# stepper_cape.net
KiCad netlist of a schematic drawn in EAGLE
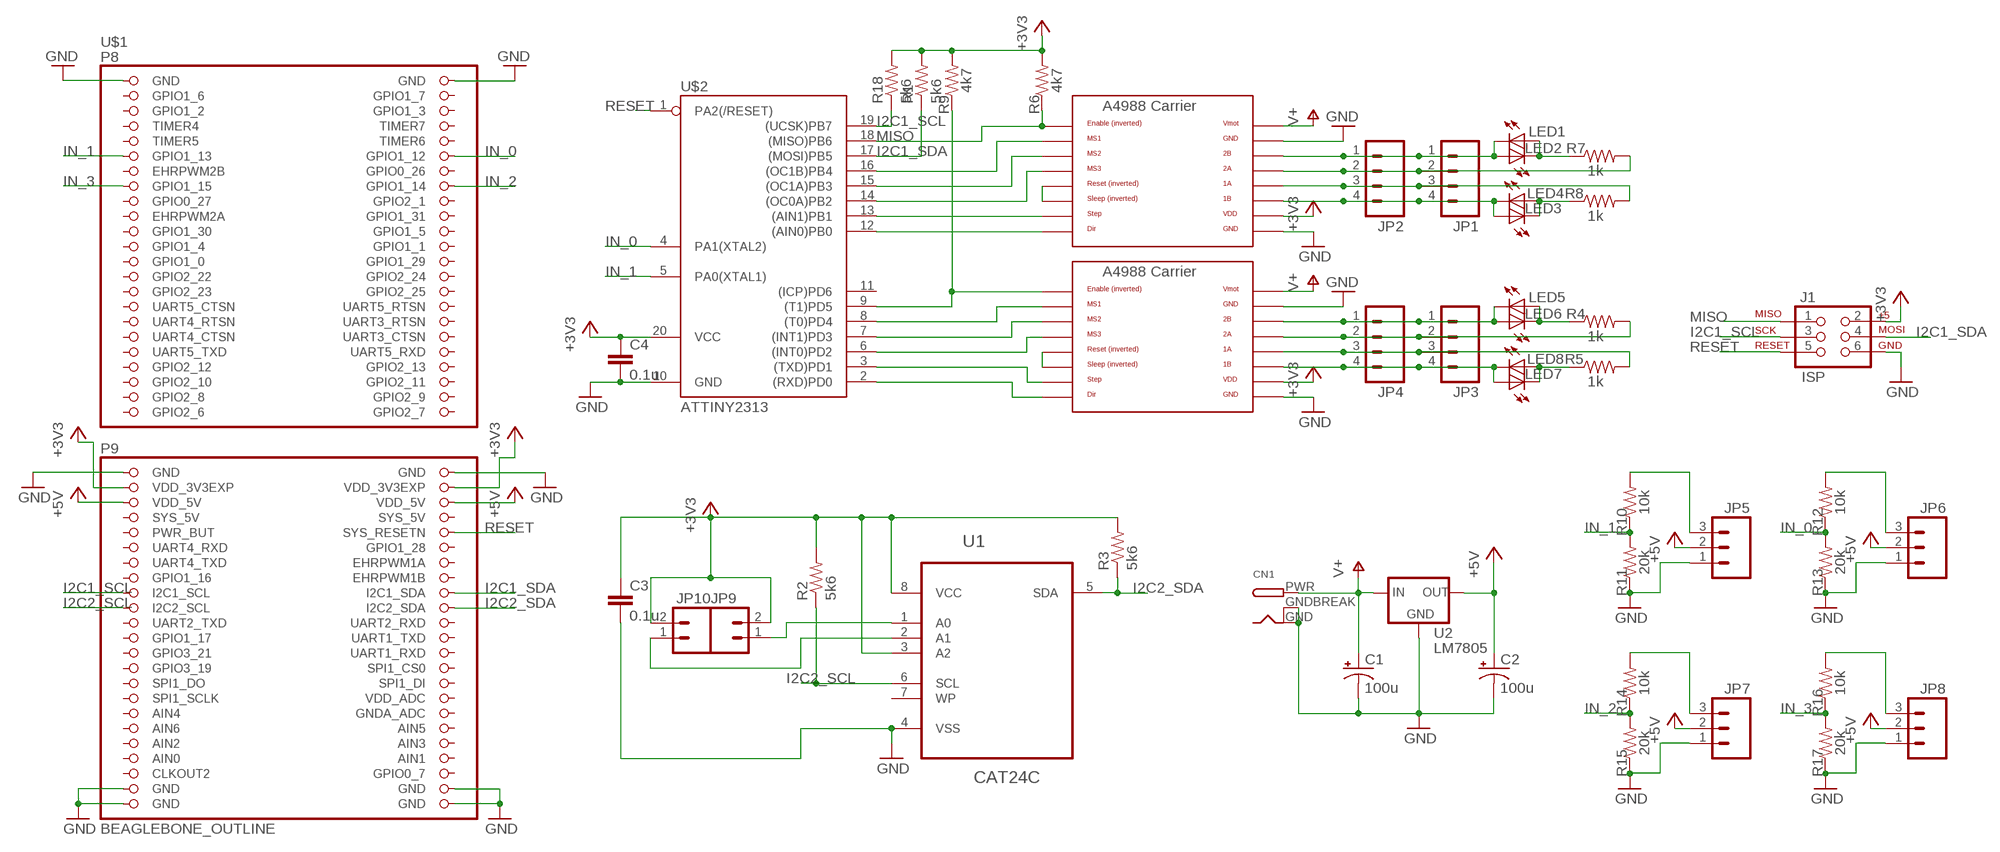
[diagram p0: schematic, sheet 1]

(export (version "E")
  (design (tool "Eeschema 10.0.6"))
  (components
    (comp (ref "C1")
      (value "100u")
      (footprint "eagle-import:E2,5-6")
      (libsource (lib "eagle-import") (part "CPOL-USE2.5-6"))
    )
    (comp (ref "C2")
      (value "100u")
      (footprint "eagle-import:E2,5-6")
      (libsource (lib "eagle-import") (part "CPOL-USE2.5-6"))
    )
    (comp (ref "C3")
      (value "0.1u")
      (footprint "eagle-import:0805")
      (libsource (lib "eagle-import") (part "CAP0805"))
    )
    (comp (ref "C4")
      (value "0.1u")
      (footprint "eagle-import:0805")
      (libsource (lib "eagle-import") (part "CAP0805"))
    )
    (comp (ref "CN1")
      (value "DCBARRELPTH")
      (footprint "eagle-import:DCJACK_2MM_PTH")
      (libsource (lib "eagle-import") (part "DCBARRELPTH"))
    )
    (comp (ref "J1")
      (value "ISP")
      (footprint "eagle-import:2X3")
      (libsource (lib "eagle-import") (part "AVR_SPI_PRG_6PTH"))
    )
    (comp (ref "JP1")
      (value "M04SCREW")
      (footprint "eagle-import:SCREWTERMINAL-3.5MM-4")
      (libsource (lib "eagle-import") (part "M04SCREW"))
    )
    (comp (ref "JP2")
      (value "M04PTH")
      (footprint "eagle-import:1X04")
      (libsource (lib "eagle-import") (part "M04PTH"))
    )
    (comp (ref "JP3")
      (value "M04SCREW")
      (footprint "eagle-import:SCREWTERMINAL-3.5MM-4")
      (libsource (lib "eagle-import") (part "M04SCREW"))
    )
    (comp (ref "JP4")
      (value "M04PTH")
      (footprint "eagle-import:1X04")
      (libsource (lib "eagle-import") (part "M04PTH"))
    )
    (comp (ref "JP5")
      (value "M03PTH")
      (footprint "eagle-import:1X03")
      (libsource (lib "eagle-import") (part "M03PTH"))
    )
    (comp (ref "JP6")
      (value "M03PTH")
      (footprint "eagle-import:1X03")
      (libsource (lib "eagle-import") (part "M03PTH"))
    )
    (comp (ref "JP7")
      (value "M03PTH")
      (footprint "eagle-import:1X03")
      (libsource (lib "eagle-import") (part "M03PTH"))
    )
    (comp (ref "JP8")
      (value "M03PTH")
      (footprint "eagle-import:1X03")
      (libsource (lib "eagle-import") (part "M03PTH"))
    )
    (comp (ref "JP9")
      (value "M02PTH")
      (footprint "eagle-import:1X02")
      (libsource (lib "eagle-import") (part "M02PTH"))
    )
    (comp (ref "JP10")
      (value "M02PTH")
      (footprint "eagle-import:1X02")
      (libsource (lib "eagle-import") (part "M02PTH"))
    )
    (comp (ref "LED1")
      (value "LEDCHIPLED_1206")
      (footprint "eagle-import:CHIPLED_1206")
      (libsource (lib "eagle-import") (part "LEDCHIPLED_1206"))
    )
    (comp (ref "LED2")
      (value "LEDCHIPLED_1206")
      (footprint "eagle-import:CHIPLED_1206")
      (libsource (lib "eagle-import") (part "LEDCHIPLED_1206"))
    )
    (comp (ref "LED3")
      (value "LEDCHIPLED_1206")
      (footprint "eagle-import:CHIPLED_1206")
      (libsource (lib "eagle-import") (part "LEDCHIPLED_1206"))
    )
    (comp (ref "LED4")
      (value "LEDCHIPLED_1206")
      (footprint "eagle-import:CHIPLED_1206")
      (libsource (lib "eagle-import") (part "LEDCHIPLED_1206"))
    )
    (comp (ref "LED5")
      (value "LEDCHIPLED_1206")
      (footprint "eagle-import:CHIPLED_1206")
      (libsource (lib "eagle-import") (part "LEDCHIPLED_1206"))
    )
    (comp (ref "LED6")
      (value "LEDCHIPLED_1206")
      (footprint "eagle-import:CHIPLED_1206")
      (libsource (lib "eagle-import") (part "LEDCHIPLED_1206"))
    )
    (comp (ref "LED7")
      (value "LEDCHIPLED_1206")
      (footprint "eagle-import:CHIPLED_1206")
      (libsource (lib "eagle-import") (part "LEDCHIPLED_1206"))
    )
    (comp (ref "LED8")
      (value "LEDCHIPLED_1206")
      (footprint "eagle-import:CHIPLED_1206")
      (libsource (lib "eagle-import") (part "LEDCHIPLED_1206"))
    )
    (comp (ref "R1")
      (value "5k6")
      (footprint "eagle-import:R0805")
      (libsource (lib "eagle-import") (part "R-US_R0805"))
    )
    (comp (ref "R2")
      (value "5k6")
      (footprint "eagle-import:R0805")
      (libsource (lib "eagle-import") (part "R-US_R0805"))
    )
    (comp (ref "R3")
      (value "5k6")
      (footprint "eagle-import:R0805")
      (libsource (lib "eagle-import") (part "R-US_R0805"))
    )
    (comp (ref "R4")
      (value "1k")
      (footprint "eagle-import:R0805")
      (libsource (lib "eagle-import") (part "R-US_R0805"))
    )
    (comp (ref "R5")
      (value "1k")
      (footprint "eagle-import:R0805")
      (libsource (lib "eagle-import") (part "R-US_R0805"))
    )
    (comp (ref "R6")
      (value "4k7")
      (footprint "eagle-import:R0805")
      (libsource (lib "eagle-import") (part "R-US_R0805"))
    )
    (comp (ref "R7")
      (value "1k")
      (footprint "eagle-import:R0805")
      (libsource (lib "eagle-import") (part "R-US_R0805"))
    )
    (comp (ref "R8")
      (value "1k")
      (footprint "eagle-import:R0805")
      (libsource (lib "eagle-import") (part "R-US_R0805"))
    )
    (comp (ref "R9")
      (value "4k7")
      (footprint "eagle-import:R0805")
      (libsource (lib "eagle-import") (part "R-US_R0805"))
    )
    (comp (ref "R10")
      (value "10k")
      (footprint "eagle-import:R0805")
      (libsource (lib "eagle-import") (part "R-US_R0805"))
    )
    (comp (ref "R11")
      (value "20k")
      (footprint "eagle-import:R0805")
      (libsource (lib "eagle-import") (part "R-US_R0805"))
    )
    (comp (ref "R12")
      (value "10k")
      (footprint "eagle-import:R0805")
      (libsource (lib "eagle-import") (part "R-US_R0805"))
    )
    (comp (ref "R13")
      (value "20k")
      (footprint "eagle-import:R0805")
      (libsource (lib "eagle-import") (part "R-US_R0805"))
    )
    (comp (ref "R14")
      (value "10k")
      (footprint "eagle-import:R0805")
      (libsource (lib "eagle-import") (part "R-US_R0805"))
    )
    (comp (ref "R15")
      (value "20k")
      (footprint "eagle-import:R0805")
      (libsource (lib "eagle-import") (part "R-US_R0805"))
    )
    (comp (ref "R16")
      (value "10k")
      (footprint "eagle-import:R0805")
      (libsource (lib "eagle-import") (part "R-US_R0805"))
    )
    (comp (ref "R17")
      (value "20k")
      (footprint "eagle-import:R0805")
      (libsource (lib "eagle-import") (part "R-US_R0805"))
    )
    (comp (ref "R18")
      (value "5k6")
      (footprint "eagle-import:R0805")
      (libsource (lib "eagle-import") (part "R-US_R0805"))
    )
    (comp (ref "U$1")
      (value "BEAGLEBONE_OUTLINE")
      (footprint "eagle-import:BEAGLEBONE_SHIELD")
      (libsource (lib "eagle-import") (part "BEAGLEBONE_OUTLINE"))
    )
    (comp (ref "U$2")
      (value "ATTINY2313")
      (footprint "eagle-import:SO20L$")
      (libsource (lib "eagle-import") (part "TINY2313-S"))
    )
    (comp (ref "U1")
      (value "CAT24C")
      (footprint "eagle-import:SOIC127P600X175-8N")
      (fields (field (name "MPN") "CAT24C256WI-GT3"))
      (libsource (lib "eagle-import") (part "CAT24C256WI-GT3"))
    )
    (comp (ref "U2")
      (value "LM7805")
      (footprint "eagle-import:TO220-IGO")
      (libsource (lib "eagle-import") (part "V_REG_78XXSINK"))
    )
    (comp (ref "X")
      (value "A4988BREAKOUT")
      (footprint "eagle-import:A4988BREAKOUT")
      (libsource (lib "eagle-import") (part "A4988BREAKOUT"))
    )
    (comp (ref "X1")
      (value "A4988BREAKOUT")
      (footprint "eagle-import:A4988BREAKOUT")
      (libsource (lib "eagle-import") (part "A4988BREAKOUT"))
    )
  )
  (nets
    (net (code "1") (name "+3V3") (class "Default")
      (node (ref "C3") (pin "1") (pinfunction "1_1") (pintype "passive"))
      (node (ref "C4") (pin "1") (pinfunction "1_1") (pintype "passive"))
      (node (ref "J1") (pin "2") (pinfunction "2_2") (pintype "passive"))
      (node (ref "JP10") (pin "2") (pinfunction "2_2") (pintype "passive"))
      (node (ref "JP9") (pin "2") (pinfunction "2_2") (pintype "passive"))
      (node (ref "R1") (pin "2") (pinfunction "2_2") (pintype "passive"))
      (node (ref "R18") (pin "2") (pinfunction "2_2") (pintype "passive"))
      (node (ref "R2") (pin "2") (pinfunction "2_2") (pintype "passive"))
      (node (ref "R3") (pin "2") (pinfunction "2_2") (pintype "passive"))
      (node (ref "R6") (pin "2") (pinfunction "2_2") (pintype "passive"))
      (node (ref "R9") (pin "2") (pinfunction "2_2") (pintype "passive"))
      (node (ref "U$1") (pin "49") (pinfunction "VDD_3V3EXP_49") (pintype "power_in"))
      (node (ref "U$1") (pin "50") (pinfunction "VDD_3V3EXP_50") (pintype "power_in"))
      (node (ref "U$2") (pin "20") (pinfunction "VCC_20") (pintype "power_in"))
      (node (ref "U1") (pin "3") (pinfunction "A2_3") (pintype "input"))
      (node (ref "U1") (pin "8") (pinfunction "VCC_8") (pintype "power_in"))
      (node (ref "X") (pin "VDD") (pinfunction "VDD_VDD") (pintype "power_in"))
      (node (ref "X1") (pin "VDD") (pinfunction "VDD_VDD") (pintype "power_in"))
    )
    (net (code "2") (name "+5V") (class "Default")
      (node (ref "C2") (pin "+") (pinfunction "+_+") (pintype "passive"))
      (node (ref "JP5") (pin "2") (pinfunction "2_2") (pintype "passive"))
      (node (ref "JP6") (pin "2") (pinfunction "2_2") (pintype "passive"))
      (node (ref "JP7") (pin "2") (pinfunction "2_2") (pintype "passive"))
      (node (ref "JP8") (pin "2") (pinfunction "2_2") (pintype "passive"))
      (node (ref "U$1") (pin "51") (pinfunction "VDD_5V_51") (pintype "power_in"))
      (node (ref "U$1") (pin "52") (pinfunction "VDD_5V_52") (pintype "power_in"))
      (node (ref "U2") (pin "OUT") (pinfunction "OUT_OUT") (pintype "output"))
    )
    (net (code "3") (name "/AIN0") (class "Default")
      (node (ref "U$1") (pin "85") (pinfunction "AIN0_85") (pintype "power_in"))
    )
    (net (code "4") (name "/AIN3") (class "Default")
      (node (ref "U$1") (pin "84") (pinfunction "AIN3_84") (pintype "power_in"))
    )
    (net (code "5") (name "/GPIO1_6") (class "Default")
      (node (ref "U$1") (pin "3") (pinfunction "GPIO1_6_3") (pintype "power_in"))
    )
    (net (code "6") (name "/GPIO1_7") (class "Default")
      (node (ref "U$1") (pin "4") (pinfunction "GPIO1_7_4") (pintype "power_in"))
    )
    (net (code "7") (name "/GPIO2_6") (class "Default")
      (node (ref "U$1") (pin "45") (pinfunction "GPIO2_6_45") (pintype "power_in"))
    )
    (net (code "8") (name "/GPIO2_7") (class "Default")
      (node (ref "U$1") (pin "46") (pinfunction "GPIO2_7_46") (pintype "power_in"))
    )
    (net (code "9") (name "/GPIO2_8") (class "Default")
      (node (ref "U$1") (pin "43") (pinfunction "GPIO2_8_43") (pintype "power_in"))
    )
    (net (code "10") (name "/GPIO2_9") (class "Default")
      (node (ref "U$1") (pin "44") (pinfunction "GPIO2_9_44") (pintype "power_in"))
    )
    (net (code "11") (name "/GPIO2_11") (class "Default")
      (node (ref "U$1") (pin "42") (pinfunction "GPIO2_11_42") (pintype "power_in"))
    )
    (net (code "12") (name "/I2C1_SCL") (class "Default")
      (node (ref "J1") (pin "3") (pinfunction "3_3") (pintype "passive"))
      (node (ref "R18") (pin "1") (pinfunction "1_1") (pintype "passive"))
      (node (ref "U$1") (pin "63") (pinfunction "I2C1_SCL_63") (pintype "passive"))
      (node (ref "U$2") (pin "19") (pinfunction "(UCSK)PB7_19") (pintype "bidirectional"))
    )
    (net (code "13") (name "/I2C1_SDA") (class "Default")
      (node (ref "J1") (pin "4") (pinfunction "4_4") (pintype "passive"))
      (node (ref "R1") (pin "1") (pinfunction "1_1") (pintype "passive"))
      (node (ref "U$1") (pin "64") (pinfunction "I2C1_SDA_64") (pintype "passive"))
      (node (ref "U$2") (pin "17") (pinfunction "(MOSI)PB5_17") (pintype "bidirectional"))
    )
    (net (code "14") (name "/I2C2_SCL") (class "Default")
      (node (ref "R2") (pin "1") (pinfunction "1_1") (pintype "passive"))
      (node (ref "U$1") (pin "65") (pinfunction "I2C2_SCL_65") (pintype "passive"))
      (node (ref "U1") (pin "6") (pinfunction "SCL_6") (pintype "input"))
    )
    (net (code "15") (name "/I2C2_SDA") (class "Default")
      (node (ref "R3") (pin "1") (pinfunction "1_1") (pintype "passive"))
      (node (ref "U$1") (pin "66") (pinfunction "I2C2_SDA_66") (pintype "passive"))
      (node (ref "U1") (pin "5") (pinfunction "SDA_5") (pintype "bidirectional"))
    )
    (net (code "16") (name "/IN_0") (class "Default")
      (node (ref "R12") (pin "1") (pinfunction "1_1") (pintype "passive"))
      (node (ref "R13") (pin "2") (pinfunction "2_2") (pintype "passive"))
      (node (ref "U$1") (pin "12") (pinfunction "GPIO1_12_12") (pintype "passive"))
      (node (ref "U$2") (pin "4") (pinfunction "PA1(XTAL2)_4") (pintype "bidirectional"))
    )
    (net (code "17") (name "/IN_1") (class "Default")
      (node (ref "R10") (pin "1") (pinfunction "1_1") (pintype "passive"))
      (node (ref "R11") (pin "2") (pinfunction "2_2") (pintype "passive"))
      (node (ref "U$1") (pin "11") (pinfunction "GPIO1_13_11") (pintype "passive"))
      (node (ref "U$2") (pin "5") (pinfunction "PA0(XTAL1)_5") (pintype "bidirectional"))
    )
    (net (code "18") (name "/IN_2") (class "Default")
      (node (ref "R14") (pin "1") (pinfunction "1_1") (pintype "passive"))
      (node (ref "R15") (pin "2") (pinfunction "2_2") (pintype "passive"))
      (node (ref "U$1") (pin "16") (pinfunction "GPIO1_14_16") (pintype "passive"))
    )
    (net (code "19") (name "/IN_3") (class "Default")
      (node (ref "R16") (pin "1") (pinfunction "1_1") (pintype "passive"))
      (node (ref "R17") (pin "2") (pinfunction "2_2") (pintype "passive"))
      (node (ref "U$1") (pin "15") (pinfunction "GPIO1_15_15") (pintype "passive"))
    )
    (net (code "20") (name "/MISO") (class "Default")
      (node (ref "J1") (pin "1") (pinfunction "1_1") (pintype "passive"))
      (node (ref "R6") (pin "1") (pinfunction "1_1") (pintype "passive"))
      (node (ref "U$2") (pin "18") (pinfunction "(MISO)PB6_18") (pintype "bidirectional"))
      (node (ref "X") (pin "EN") (pinfunction "EN_EN") (pintype "input"))
    )
    (net (code "21") (name "/RESET") (class "Default")
      (node (ref "J1") (pin "5") (pinfunction "5_5") (pintype "passive"))
      (node (ref "U$1") (pin "56") (pinfunction "SYS_RESETN_56") (pintype "passive"))
      (node (ref "U$2") (pin "1") (pinfunction "PA2(/RESET)_1") (pintype "input"))
    )
    (net (code "22") (name "GND") (class "Default")
      (node (ref "C1") (pin "-") (pinfunction "-_-") (pintype "passive"))
      (node (ref "C2") (pin "-") (pinfunction "-_-") (pintype "passive"))
      (node (ref "C3") (pin "2") (pinfunction "2_2") (pintype "passive"))
      (node (ref "C4") (pin "2") (pinfunction "2_2") (pintype "passive"))
      (node (ref "CN1") (pin "GND") (pinfunction "GND_GND") (pintype "power_in"))
      (node (ref "CN1") (pin "GNDBREAK") (pinfunction "GNDBREAK_GNDBREAK") (pintype "power_in"))
      (node (ref "J1") (pin "6") (pinfunction "6_6") (pintype "passive"))
      (node (ref "JP5") (pin "1") (pinfunction "1_1") (pintype "passive"))
      (node (ref "JP6") (pin "1") (pinfunction "1_1") (pintype "passive"))
      (node (ref "JP7") (pin "1") (pinfunction "1_1") (pintype "passive"))
      (node (ref "JP8") (pin "1") (pinfunction "1_1") (pintype "passive"))
      (node (ref "R11") (pin "1") (pinfunction "1_1") (pintype "passive"))
      (node (ref "R13") (pin "1") (pinfunction "1_1") (pintype "passive"))
      (node (ref "R15") (pin "1") (pinfunction "1_1") (pintype "passive"))
      (node (ref "R17") (pin "1") (pinfunction "1_1") (pintype "passive"))
      (node (ref "U$1") (pin "1") (pinfunction "GND_1") (pintype "power_in"))
      (node (ref "U$1") (pin "2") (pinfunction "GND_2") (pintype "power_in"))
      (node (ref "U$1") (pin "47") (pinfunction "GND_47") (pintype "power_in"))
      (node (ref "U$1") (pin "48") (pinfunction "GND_48") (pintype "power_in"))
      (node (ref "U$1") (pin "89") (pinfunction "GND_89") (pintype "input"))
      (node (ref "U$1") (pin "90") (pinfunction "GND_90") (pintype "input"))
      (node (ref "U$1") (pin "91") (pinfunction "GND_91") (pintype "input"))
      (node (ref "U$1") (pin "92") (pinfunction "GND_92") (pintype "input"))
      (node (ref "U$2") (pin "10") (pinfunction "GND_10") (pintype "power_in"))
      (node (ref "U1") (pin "4") (pinfunction "VSS_4") (pintype "passive"))
      (node (ref "U2") (pin "GND") (pinfunction "GND_GND") (pintype "input"))
      (node (ref "X") (pin "GND") (pinfunction "GND_GND") (pintype "power_in"))
      (node (ref "X") (pin "GND@0") (pinfunction "GND_GND@0") (pintype "power_in"))
      (node (ref "X1") (pin "GND") (pinfunction "GND_GND") (pintype "power_in"))
      (node (ref "X1") (pin "GND@0") (pinfunction "GND_GND@0") (pintype "power_in"))
    )
    (net (code "23") (name "Net-(JP1-Pad1)") (class "Default")
      (node (ref "JP1") (pin "1") (pinfunction "1_1") (pintype "passive"))
      (node (ref "JP2") (pin "1") (pinfunction "1_1") (pintype "passive"))
      (node (ref "LED1") (pin "C") (pinfunction "C_C") (pintype "passive"))
      (node (ref "LED2") (pin "A") (pinfunction "A_A") (pintype "passive"))
      (node (ref "X") (pin "2B") (pinfunction "2B_2B") (pintype "output"))
    )
    (net (code "24") (name "Net-(JP1-Pad2)") (class "Default")
      (node (ref "JP1") (pin "2") (pinfunction "2_2") (pintype "passive"))
      (node (ref "JP2") (pin "2") (pinfunction "2_2") (pintype "passive"))
      (node (ref "R7") (pin "2") (pinfunction "2_2") (pintype "passive"))
      (node (ref "X") (pin "2A") (pinfunction "2A_2A") (pintype "output"))
    )
    (net (code "25") (name "Net-(JP1-Pad3)") (class "Default")
      (node (ref "JP1") (pin "3") (pinfunction "3_3") (pintype "passive"))
      (node (ref "JP2") (pin "3") (pinfunction "3_3") (pintype "passive"))
      (node (ref "R8") (pin "2") (pinfunction "2_2") (pintype "passive"))
      (node (ref "X") (pin "1A") (pinfunction "1A_1A") (pintype "output"))
    )
    (net (code "26") (name "Net-(JP1-Pad4)") (class "Default")
      (node (ref "JP1") (pin "4") (pinfunction "4_4") (pintype "passive"))
      (node (ref "JP2") (pin "4") (pinfunction "4_4") (pintype "passive"))
      (node (ref "LED3") (pin "A") (pinfunction "A_A") (pintype "passive"))
      (node (ref "LED4") (pin "C") (pinfunction "C_C") (pintype "passive"))
      (node (ref "X") (pin "1B") (pinfunction "1B_1B") (pintype "output"))
    )
    (net (code "27") (name "Net-(JP3-Pad1)") (class "Default")
      (node (ref "JP3") (pin "1") (pinfunction "1_1") (pintype "passive"))
      (node (ref "JP4") (pin "1") (pinfunction "1_1") (pintype "passive"))
      (node (ref "LED5") (pin "C") (pinfunction "C_C") (pintype "passive"))
      (node (ref "LED6") (pin "A") (pinfunction "A_A") (pintype "passive"))
      (node (ref "X1") (pin "2B") (pinfunction "2B_2B") (pintype "output"))
    )
    (net (code "28") (name "Net-(JP3-Pad2)") (class "Default")
      (node (ref "JP3") (pin "2") (pinfunction "2_2") (pintype "passive"))
      (node (ref "JP4") (pin "2") (pinfunction "2_2") (pintype "passive"))
      (node (ref "R4") (pin "2") (pinfunction "2_2") (pintype "passive"))
      (node (ref "X1") (pin "2A") (pinfunction "2A_2A") (pintype "output"))
    )
    (net (code "29") (name "Net-(JP3-Pad3)") (class "Default")
      (node (ref "JP3") (pin "3") (pinfunction "3_3") (pintype "passive"))
      (node (ref "JP4") (pin "3") (pinfunction "3_3") (pintype "passive"))
      (node (ref "R5") (pin "2") (pinfunction "2_2") (pintype "passive"))
      (node (ref "X1") (pin "1A") (pinfunction "1A_1A") (pintype "output"))
    )
    (net (code "30") (name "Net-(JP3-Pad4)") (class "Default")
      (node (ref "JP3") (pin "4") (pinfunction "4_4") (pintype "passive"))
      (node (ref "JP4") (pin "4") (pinfunction "4_4") (pintype "passive"))
      (node (ref "LED7") (pin "A") (pinfunction "A_A") (pintype "passive"))
      (node (ref "LED8") (pin "C") (pinfunction "C_C") (pintype "passive"))
      (node (ref "X1") (pin "1B") (pinfunction "1B_1B") (pintype "output"))
    )
    (net (code "31") (name "Net-(JP5-Pad3)") (class "Default")
      (node (ref "JP5") (pin "3") (pinfunction "3_3") (pintype "passive"))
      (node (ref "R10") (pin "2") (pinfunction "2_2") (pintype "passive"))
    )
    (net (code "32") (name "Net-(JP6-Pad3)") (class "Default")
      (node (ref "JP6") (pin "3") (pinfunction "3_3") (pintype "passive"))
      (node (ref "R12") (pin "2") (pinfunction "2_2") (pintype "passive"))
    )
    (net (code "33") (name "Net-(JP7-Pad3)") (class "Default")
      (node (ref "JP7") (pin "3") (pinfunction "3_3") (pintype "passive"))
      (node (ref "R14") (pin "2") (pinfunction "2_2") (pintype "passive"))
    )
    (net (code "34") (name "Net-(JP8-Pad3)") (class "Default")
      (node (ref "JP8") (pin "3") (pinfunction "3_3") (pintype "passive"))
      (node (ref "R16") (pin "2") (pinfunction "2_2") (pintype "passive"))
    )
    (net (code "35") (name "Net-(LED1-PadA)") (class "Default")
      (node (ref "LED1") (pin "A") (pinfunction "A_A") (pintype "passive"))
      (node (ref "LED2") (pin "C") (pinfunction "C_C") (pintype "passive"))
      (node (ref "R7") (pin "1") (pinfunction "1_1") (pintype "passive"))
    )
    (net (code "36") (name "Net-(LED3-PadC)") (class "Default")
      (node (ref "LED3") (pin "C") (pinfunction "C_C") (pintype "passive"))
      (node (ref "LED4") (pin "A") (pinfunction "A_A") (pintype "passive"))
      (node (ref "R8") (pin "1") (pinfunction "1_1") (pintype "passive"))
    )
    (net (code "37") (name "Net-(LED5-PadA)") (class "Default")
      (node (ref "LED5") (pin "A") (pinfunction "A_A") (pintype "passive"))
      (node (ref "LED6") (pin "C") (pinfunction "C_C") (pintype "passive"))
      (node (ref "R4") (pin "1") (pinfunction "1_1") (pintype "passive"))
    )
    (net (code "38") (name "Net-(LED7-PadC)") (class "Default")
      (node (ref "LED7") (pin "C") (pinfunction "C_C") (pintype "passive"))
      (node (ref "LED8") (pin "A") (pinfunction "A_A") (pintype "passive"))
      (node (ref "R5") (pin "1") (pinfunction "1_1") (pintype "passive"))
    )
    (net (code "39") (name "Net-(U$2-(AIN0)PB0)") (class "Default")
      (node (ref "U$2") (pin "12") (pinfunction "(AIN0)PB0_12") (pintype "bidirectional"))
      (node (ref "X") (pin "DIR") (pinfunction "DIR_DIR") (pintype "input"))
    )
    (net (code "40") (name "Net-(U$2-(AIN1)PB1)") (class "Default")
      (node (ref "U$2") (pin "13") (pinfunction "(AIN1)PB1_13") (pintype "bidirectional"))
      (node (ref "X") (pin "STEP") (pinfunction "STEP_STEP") (pintype "input"))
    )
    (net (code "41") (name "Net-(U$2-(INT0)PD2)") (class "Default")
      (node (ref "U$2") (pin "6") (pinfunction "(INT0)PD2_6") (pintype "bidirectional"))
      (node (ref "X1") (pin "MS3") (pinfunction "MS3_MS3") (pintype "input"))
    )
    (net (code "42") (name "Net-(U$2-(INT1)PD3)") (class "Default")
      (node (ref "U$2") (pin "7") (pinfunction "(INT1)PD3_7") (pintype "bidirectional"))
      (node (ref "X1") (pin "MS2") (pinfunction "MS2_MS2") (pintype "input"))
    )
    (net (code "43") (name "Net-(U$2-(OC0A)PB2)") (class "Default")
      (node (ref "U$2") (pin "14") (pinfunction "(OC0A)PB2_14") (pintype "bidirectional"))
      (node (ref "X") (pin "MS3") (pinfunction "MS3_MS3") (pintype "input"))
    )
    (net (code "44") (name "Net-(U$2-(OC1A)PB3)") (class "Default")
      (node (ref "U$2") (pin "15") (pinfunction "(OC1A)PB3_15") (pintype "bidirectional"))
      (node (ref "X") (pin "MS2") (pinfunction "MS2_MS2") (pintype "input"))
    )
    (net (code "45") (name "Net-(U$2-(OC1B)PB4)") (class "Default")
      (node (ref "U$2") (pin "16") (pinfunction "(OC1B)PB4_16") (pintype "bidirectional"))
      (node (ref "X") (pin "MS1") (pinfunction "MS1_MS1") (pintype "input"))
    )
    (net (code "46") (name "Net-(U$2-(RXD)PD0)") (class "Default")
      (node (ref "U$2") (pin "2") (pinfunction "(RXD)PD0_2") (pintype "bidirectional"))
      (node (ref "X1") (pin "DIR") (pinfunction "DIR_DIR") (pintype "input"))
    )
    (net (code "47") (name "Net-(U$2-(T0)PD4)") (class "Default")
      (node (ref "U$2") (pin "8") (pinfunction "(T0)PD4_8") (pintype "bidirectional"))
      (node (ref "X1") (pin "MS1") (pinfunction "MS1_MS1") (pintype "input"))
    )
    (net (code "48") (name "Net-(U$2-(T1)PD5)") (class "Default")
      (node (ref "R9") (pin "1") (pinfunction "1_1") (pintype "passive"))
      (node (ref "U$2") (pin "9") (pinfunction "(T1)PD5_9") (pintype "bidirectional"))
      (node (ref "X1") (pin "EN") (pinfunction "EN_EN") (pintype "input"))
    )
    (net (code "49") (name "Net-(U$2-(TXD)PD1)") (class "Default")
      (node (ref "U$2") (pin "3") (pinfunction "(TXD)PD1_3") (pintype "bidirectional"))
      (node (ref "X1") (pin "STEP") (pinfunction "STEP_STEP") (pintype "input"))
    )
    (net (code "50") (name "Net-(U1-A0)") (class "Default")
      (node (ref "JP9") (pin "1") (pinfunction "1_1") (pintype "passive"))
      (node (ref "U1") (pin "1") (pinfunction "A0_1") (pintype "input"))
    )
    (net (code "51") (name "Net-(U1-A1)") (class "Default")
      (node (ref "JP10") (pin "1") (pinfunction "1_1") (pintype "passive"))
      (node (ref "U1") (pin "2") (pinfunction "A1_2") (pintype "input"))
    )
    (net (code "52") (name "Net-(X-SLEEP)") (class "Default")
      (node (ref "X") (pin "RST") (pinfunction "RST_RST") (pintype "input"))
      (node (ref "X") (pin "SLP") (pinfunction "SLEEP_SLP") (pintype "input"))
    )
    (net (code "53") (name "Net-(X1-SLEEP)") (class "Default")
      (node (ref "X1") (pin "RST") (pinfunction "RST_RST") (pintype "input"))
      (node (ref "X1") (pin "SLP") (pinfunction "SLEEP_SLP") (pintype "input"))
    )
    (net (code "54") (name "V+") (class "Default")
      (node (ref "C1") (pin "+") (pinfunction "+_+") (pintype "passive"))
      (node (ref "CN1") (pin "PWR") (pinfunction "PWR_PWR") (pintype "power_in"))
      (node (ref "U2") (pin "IN") (pinfunction "IN_IN") (pintype "input"))
      (node (ref "X") (pin "VMOT") (pinfunction "VMOT_VMOT") (pintype "power_in"))
      (node (ref "X1") (pin "VMOT") (pinfunction "VMOT_VMOT") (pintype "power_in"))
    )
    (net (code "55") (name "unconnected-(U$1-AIN1-Pad86)") (class "Default")
      (node (ref "U$1") (pin "86") (pinfunction "AIN1_86") (pintype "input"))
    )
    (net (code "56") (name "unconnected-(U$1-AIN2-Pad83)") (class "Default")
      (node (ref "U$1") (pin "83") (pinfunction "AIN2_83") (pintype "passive"))
    )
    (net (code "57") (name "unconnected-(U$1-AIN4-Pad79)") (class "Default")
      (node (ref "U$1") (pin "79") (pinfunction "AIN4_79") (pintype "passive"))
    )
    (net (code "58") (name "unconnected-(U$1-AIN5-Pad82)") (class "Default")
      (node (ref "U$1") (pin "82") (pinfunction "AIN5_82") (pintype "passive"))
    )
    (net (code "59") (name "unconnected-(U$1-AIN6-Pad81)") (class "Default")
      (node (ref "U$1") (pin "81") (pinfunction "AIN6_81") (pintype "passive"))
    )
    (net (code "60") (name "unconnected-(U$1-CLKOUT2-Pad87)") (class "Default")
      (node (ref "U$1") (pin "87") (pinfunction "CLKOUT2_87") (pintype "input"))
    )
    (net (code "61") (name "unconnected-(U$1-EHRPWM1A-Pad60)") (class "Default")
      (node (ref "U$1") (pin "60") (pinfunction "EHRPWM1A_60") (pintype "passive"))
    )
    (net (code "62") (name "unconnected-(U$1-EHRPWM1B-Pad62)") (class "Default")
      (node (ref "U$1") (pin "62") (pinfunction "EHRPWM1B_62") (pintype "passive"))
    )
    (net (code "63") (name "unconnected-(U$1-EHRPWM2A-Pad19)") (class "Default")
      (node (ref "U$1") (pin "19") (pinfunction "EHRPWM2A_19") (pintype "passive"))
    )
    (net (code "64") (name "unconnected-(U$1-EHRPWM2B-Pad13)") (class "Default")
      (node (ref "U$1") (pin "13") (pinfunction "EHRPWM2B_13") (pintype "passive"))
    )
    (net (code "65") (name "unconnected-(U$1-GNDA_ADC-Pad80)") (class "Default")
      (node (ref "U$1") (pin "80") (pinfunction "GNDA_ADC_80") (pintype "passive"))
    )
    (net (code "66") (name "unconnected-(U$1-GPIO0_7-Pad88)") (class "Default")
      (node (ref "U$1") (pin "88") (pinfunction "GPIO0_7_88") (pintype "input"))
    )
    (net (code "67") (name "unconnected-(U$1-GPIO0_26-Pad14)") (class "Default")
      (node (ref "U$1") (pin "14") (pinfunction "GPIO0_26_14") (pintype "passive"))
    )
    (net (code "68") (name "unconnected-(U$1-GPIO0_27-Pad17)") (class "Default")
      (node (ref "U$1") (pin "17") (pinfunction "GPIO0_27_17") (pintype "passive"))
    )
    (net (code "69") (name "unconnected-(U$1-GPIO1_0-Pad25)") (class "Default")
      (node (ref "U$1") (pin "25") (pinfunction "GPIO1_0_25") (pintype "passive"))
    )
    (net (code "70") (name "unconnected-(U$1-GPIO1_1-Pad24)") (class "Default")
      (node (ref "U$1") (pin "24") (pinfunction "GPIO1_1_24") (pintype "passive"))
    )
    (net (code "71") (name "unconnected-(U$1-GPIO1_2-Pad5)") (class "Default")
      (node (ref "U$1") (pin "5") (pinfunction "GPIO1_2_5") (pintype "passive"))
    )
    (net (code "72") (name "unconnected-(U$1-GPIO1_3-Pad6)") (class "Default")
      (node (ref "U$1") (pin "6") (pinfunction "GPIO1_3_6") (pintype "passive"))
    )
    (net (code "73") (name "unconnected-(U$1-GPIO1_4-Pad23)") (class "Default")
      (node (ref "U$1") (pin "23") (pinfunction "GPIO1_4_23") (pintype "passive"))
    )
    (net (code "74") (name "unconnected-(U$1-GPIO1_5-Pad22)") (class "Default")
      (node (ref "U$1") (pin "22") (pinfunction "GPIO1_5_22") (pintype "passive"))
    )
    (net (code "75") (name "unconnected-(U$1-GPIO1_16-Pad61)") (class "Default")
      (node (ref "U$1") (pin "61") (pinfunction "GPIO1_16_61") (pintype "passive"))
    )
    (net (code "76") (name "unconnected-(U$1-GPIO1_17-Pad69)") (class "Default")
      (node (ref "U$1") (pin "69") (pinfunction "GPIO1_17_69") (pintype "passive"))
    )
    (net (code "77") (name "unconnected-(U$1-GPIO1_28-Pad58)") (class "Default")
      (node (ref "U$1") (pin "58") (pinfunction "GPIO1_28_58") (pintype "passive"))
    )
    (net (code "78") (name "unconnected-(U$1-GPIO1_29-Pad26)") (class "Default")
      (node (ref "U$1") (pin "26") (pinfunction "GPIO1_29_26") (pintype "passive"))
    )
    (net (code "79") (name "unconnected-(U$1-GPIO1_30-Pad21)") (class "Default")
      (node (ref "U$1") (pin "21") (pinfunction "GPIO1_30_21") (pintype "passive"))
    )
    (net (code "80") (name "unconnected-(U$1-GPIO1_31-Pad20)") (class "Default")
      (node (ref "U$1") (pin "20") (pinfunction "GPIO1_31_20") (pintype "passive"))
    )
    (net (code "81") (name "unconnected-(U$1-GPIO2_1-Pad18)") (class "Default")
      (node (ref "U$1") (pin "18") (pinfunction "GPIO2_1_18") (pintype "passive"))
    )
    (net (code "82") (name "unconnected-(U$1-GPIO2_10-Pad41)") (class "Default")
      (node (ref "U$1") (pin "41") (pinfunction "GPIO2_10_41") (pintype "passive"))
    )
    (net (code "83") (name "unconnected-(U$1-GPIO2_12-Pad39)") (class "Default")
      (node (ref "U$1") (pin "39") (pinfunction "GPIO2_12_39") (pintype "passive"))
    )
    (net (code "84") (name "unconnected-(U$1-GPIO2_13-Pad40)") (class "Default")
      (node (ref "U$1") (pin "40") (pinfunction "GPIO2_13_40") (pintype "passive"))
    )
    (net (code "85") (name "unconnected-(U$1-GPIO2_22-Pad27)") (class "Default")
      (node (ref "U$1") (pin "27") (pinfunction "GPIO2_22_27") (pintype "passive"))
    )
    (net (code "86") (name "unconnected-(U$1-GPIO2_23-Pad29)") (class "Default")
      (node (ref "U$1") (pin "29") (pinfunction "GPIO2_23_29") (pintype "passive"))
    )
    (net (code "87") (name "unconnected-(U$1-GPIO2_24-Pad28)") (class "Default")
      (node (ref "U$1") (pin "28") (pinfunction "GPIO2_24_28") (pintype "passive"))
    )
    (net (code "88") (name "unconnected-(U$1-GPIO2_25-Pad30)") (class "Default")
      (node (ref "U$1") (pin "30") (pinfunction "GPIO2_25_30") (pintype "passive"))
    )
    (net (code "89") (name "unconnected-(U$1-GPIO3_19-Pad73)") (class "Default")
      (node (ref "U$1") (pin "73") (pinfunction "GPIO3_19_73") (pintype "passive"))
    )
    (net (code "90") (name "unconnected-(U$1-GPIO3_21-Pad71)") (class "Default")
      (node (ref "U$1") (pin "71") (pinfunction "GPIO3_21_71") (pintype "passive"))
    )
    (net (code "91") (name "unconnected-(U$1-PWR_BUT-Pad55)") (class "Default")
      (node (ref "U$1") (pin "55") (pinfunction "PWR_BUT_55") (pintype "passive"))
    )
    (net (code "92") (name "unconnected-(U$1-SPI1_CS0-Pad74)") (class "Default")
      (node (ref "U$1") (pin "74") (pinfunction "SPI1_CS0_74") (pintype "passive"))
    )
    (net (code "93") (name "unconnected-(U$1-SPI1_DI-Pad76)") (class "Default")
      (node (ref "U$1") (pin "76") (pinfunction "SPI1_DI_76") (pintype "passive"))
    )
    (net (code "94") (name "unconnected-(U$1-SPI1_DO-Pad75)") (class "Default")
      (node (ref "U$1") (pin "75") (pinfunction "SPI1_DO_75") (pintype "passive"))
    )
    (net (code "95") (name "unconnected-(U$1-SPI1_SCLK-Pad77)") (class "Default")
      (node (ref "U$1") (pin "77") (pinfunction "SPI1_SCLK_77") (pintype "passive"))
    )
    (net (code "96") (name "unconnected-(U$1-SYS_5V-Pad53)") (class "Default")
      (node (ref "U$1") (pin "53") (pinfunction "SYS_5V_53") (pintype "passive"))
    )
    (net (code "97") (name "unconnected-(U$1-SYS_5V-Pad54)") (class "Default")
      (node (ref "U$1") (pin "54") (pinfunction "SYS_5V_54") (pintype "passive"))
    )
    (net (code "98") (name "unconnected-(U$1-TIMER4-Pad7)") (class "Default")
      (node (ref "U$1") (pin "7") (pinfunction "TIMER4_7") (pintype "passive"))
    )
    (net (code "99") (name "unconnected-(U$1-TIMER5-Pad9)") (class "Default")
      (node (ref "U$1") (pin "9") (pinfunction "TIMER5_9") (pintype "passive"))
    )
    (net (code "100") (name "unconnected-(U$1-TIMER6-Pad10)") (class "Default")
      (node (ref "U$1") (pin "10") (pinfunction "TIMER6_10") (pintype "passive"))
    )
    (net (code "101") (name "unconnected-(U$1-TIMER7-Pad8)") (class "Default")
      (node (ref "U$1") (pin "8") (pinfunction "TIMER7_8") (pintype "passive"))
    )
    (net (code "102") (name "unconnected-(U$1-UART1_RXD-Pad72)") (class "Default")
      (node (ref "U$1") (pin "72") (pinfunction "UART1_RXD_72") (pintype "passive"))
    )
    (net (code "103") (name "unconnected-(U$1-UART1_TXD-Pad70)") (class "Default")
      (node (ref "U$1") (pin "70") (pinfunction "UART1_TXD_70") (pintype "passive"))
    )
    (net (code "104") (name "unconnected-(U$1-UART2_RXD-Pad68)") (class "Default")
      (node (ref "U$1") (pin "68") (pinfunction "UART2_RXD_68") (pintype "passive"))
    )
    (net (code "105") (name "unconnected-(U$1-UART2_TXD-Pad67)") (class "Default")
      (node (ref "U$1") (pin "67") (pinfunction "UART2_TXD_67") (pintype "passive"))
    )
    (net (code "106") (name "unconnected-(U$1-UART3_CTSN-Pad36)") (class "Default")
      (node (ref "U$1") (pin "36") (pinfunction "UART3_CTSN_36") (pintype "passive"))
    )
    (net (code "107") (name "unconnected-(U$1-UART3_RTSN-Pad34)") (class "Default")
      (node (ref "U$1") (pin "34") (pinfunction "UART3_RTSN_34") (pintype "passive"))
    )
    (net (code "108") (name "unconnected-(U$1-UART4_CTSN-Pad35)") (class "Default")
      (node (ref "U$1") (pin "35") (pinfunction "UART4_CTSN_35") (pintype "passive"))
    )
    (net (code "109") (name "unconnected-(U$1-UART4_RTSN-Pad33)") (class "Default")
      (node (ref "U$1") (pin "33") (pinfunction "UART4_RTSN_33") (pintype "passive"))
    )
    (net (code "110") (name "unconnected-(U$1-UART4_RXD-Pad57)") (class "Default")
      (node (ref "U$1") (pin "57") (pinfunction "UART4_RXD_57") (pintype "passive"))
    )
    (net (code "111") (name "unconnected-(U$1-UART4_TXD-Pad59)") (class "Default")
      (node (ref "U$1") (pin "59") (pinfunction "UART4_TXD_59") (pintype "passive"))
    )
    (net (code "112") (name "unconnected-(U$1-UART5_CTSN-Pad31)") (class "Default")
      (node (ref "U$1") (pin "31") (pinfunction "UART5_CTSN_31") (pintype "passive"))
    )
    (net (code "113") (name "unconnected-(U$1-UART5_RTSN-Pad32)") (class "Default")
      (node (ref "U$1") (pin "32") (pinfunction "UART5_RTSN_32") (pintype "passive"))
    )
    (net (code "114") (name "unconnected-(U$1-UART5_RXD-Pad38)") (class "Default")
      (node (ref "U$1") (pin "38") (pinfunction "UART5_RXD_38") (pintype "passive"))
    )
    (net (code "115") (name "unconnected-(U$1-UART5_TXD-Pad37)") (class "Default")
      (node (ref "U$1") (pin "37") (pinfunction "UART5_TXD_37") (pintype "passive"))
    )
    (net (code "116") (name "unconnected-(U$1-VDD_ADC-Pad78)") (class "Default")
      (node (ref "U$1") (pin "78") (pinfunction "VDD_ADC_78") (pintype "passive"))
    )
    (net (code "117") (name "unconnected-(U$2-(ICP)PD6-Pad11)") (class "Default")
      (node (ref "U$2") (pin "11") (pinfunction "(ICP)PD6_11") (pintype "bidirectional"))
    )
    (net (code "118") (name "unconnected-(U1-WP-Pad7)") (class "Default")
      (node (ref "U1") (pin "7") (pinfunction "WP_7") (pintype "input"))
    )
  )
)
